# H-Bridge.net
KiCad netlist of a schematic drawn in Altium Designer
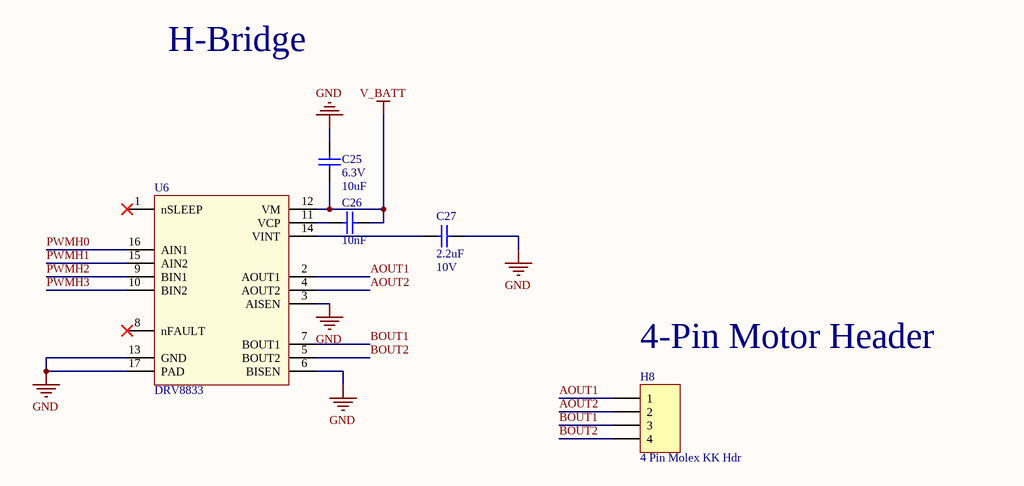
[diagram p0: H-Bridge.SchDoc]

(export (version "E")
  (design (tool "Eeschema 10.0.6"))
  (components
    (comp (ref "C25")
      (value "10uF")
      (footprint "CAPC1608L")
      (description "CAP CER 10UF X5R +-20% 6V3 0603")
      (fields (field (name "VOLTAGE - RATED") "6.3V"))
      (libsource (lib "ECE AD19Components_19V1") (part "CC_10uF_0603"))
    )
    (comp (ref "C26")
      (value "10nF")
      (footprint "CAPC1608L")
      (description "CAP CER 10nF X7R +-10% 50V 0603")
      (libsource (lib "ECE AD19Components_19V1") (part "CC_10nF_0603"))
    )
    (comp (ref "C27")
      (value "2.2uF")
      (footprint "CAPC1608L")
      (description "CAP CER 2.2uF X5R +-20% 10V 0603")
      (fields (field (name "MAX VOLTAGE") "10V"))
      (libsource (lib "ECE AD19Components_19V1") (part "CC_2.2uF_0603"))
    )
    (comp (ref "H8")
      (value "4 Pin Molex KK Hdr")
      (footprint "MOLEX_KK_4_HDR")
      (description "CONN HEADER 4POS 2.54mm VERT_Thru Hole")
      (fields (field (name "MANUFACTURER") "Molex"))
      (libsource (lib "ECE AD19Components_19V1") (part "JA_MOLEX_KK_4POS"))
    )
    (comp (ref "U6")
      (value "DRV8833")
      (footprint "HTSOP16")
      (description "Dual H-Bridge Motor Driver 1.5A")
      (libsource (lib "ENCE461AD19_19V2") (part "DRV8833"))
    )
  )
  (nets
    (net (code "1") (name "/AOUT1") (class "Default")
      (node (ref "H8") (pin "1") (pinfunction "1_1") (pintype "passive"))
      (node (ref "U6") (pin "2") (pinfunction "AOUT1_2") (pintype "passive"))
    )
    (net (code "2") (name "/AOUT2") (class "Default")
      (node (ref "H8") (pin "2") (pinfunction "2_2") (pintype "passive"))
      (node (ref "U6") (pin "4") (pinfunction "AOUT2_4") (pintype "passive"))
    )
    (net (code "3") (name "/BOUT1") (class "Default")
      (node (ref "H8") (pin "3") (pinfunction "3_3") (pintype "passive"))
      (node (ref "U6") (pin "7") (pinfunction "BOUT1_7") (pintype "passive"))
    )
    (net (code "4") (name "/BOUT2") (class "Default")
      (node (ref "H8") (pin "4") (pinfunction "4_4") (pintype "passive"))
      (node (ref "U6") (pin "5") (pinfunction "BOUT2_5") (pintype "passive"))
    )
    (net (code "5") (name "/PWMH0") (class "Default")
      (node (ref "U6") (pin "16") (pinfunction "AIN1_16") (pintype "passive"))
    )
    (net (code "6") (name "/PWMH1") (class "Default")
      (node (ref "U6") (pin "15") (pinfunction "AIN2_15") (pintype "passive"))
    )
    (net (code "7") (name "/PWMH2") (class "Default")
      (node (ref "U6") (pin "9") (pinfunction "BIN1_9") (pintype "passive"))
    )
    (net (code "8") (name "/PWMH3") (class "Default")
      (node (ref "U6") (pin "10") (pinfunction "BIN2_10") (pintype "passive"))
    )
    (net (code "9") (name "GND") (class "Default")
      (node (ref "C25") (pin "2") (pinfunction "2_2") (pintype "passive"))
      (node (ref "C27") (pin "2") (pinfunction "2_2") (pintype "passive"))
      (node (ref "U6") (pin "13") (pinfunction "GND_13") (pintype "passive"))
      (node (ref "U6") (pin "17") (pinfunction "PAD_17") (pintype "passive"))
      (node (ref "U6") (pin "3") (pinfunction "AISEN_3") (pintype "passive"))
      (node (ref "U6") (pin "6") (pinfunction "BISEN_6") (pintype "passive"))
    )
    (net (code "10") (name "Net-(U6-VCP)") (class "Default")
      (node (ref "C26") (pin "1") (pinfunction "1_1") (pintype "passive"))
      (node (ref "U6") (pin "11") (pinfunction "VCP_11") (pintype "passive"))
    )
    (net (code "11") (name "Net-(U6-VINT)") (class "Default")
      (node (ref "C27") (pin "1") (pinfunction "1_1") (pintype "passive"))
      (node (ref "U6") (pin "14") (pinfunction "VINT_14") (pintype "passive"))
    )
    (net (code "12") (name "V_BATT") (class "Default")
      (node (ref "C25") (pin "1") (pinfunction "1_1") (pintype "passive"))
      (node (ref "C26") (pin "2") (pinfunction "2_2") (pintype "passive"))
      (node (ref "U6") (pin "12") (pinfunction "VM_12") (pintype "passive"))
    )
    (net (code "13") (name "unconnected-(U6-nFAULT-Pad8)") (class "Default")
      (node (ref "U6") (pin "8") (pinfunction "nFAULT_8") (pintype "passive+no_connect"))
    )
    (net (code "14") (name "unconnected-(U6-nSLEEP-Pad1)") (class "Default")
      (node (ref "U6") (pin "1") (pinfunction "nSLEEP_1") (pintype "passive+no_connect"))
    )
  )
)
